# Usb_Hub.net
KiCad netlist of a schematic drawn in EasyEDA Pro
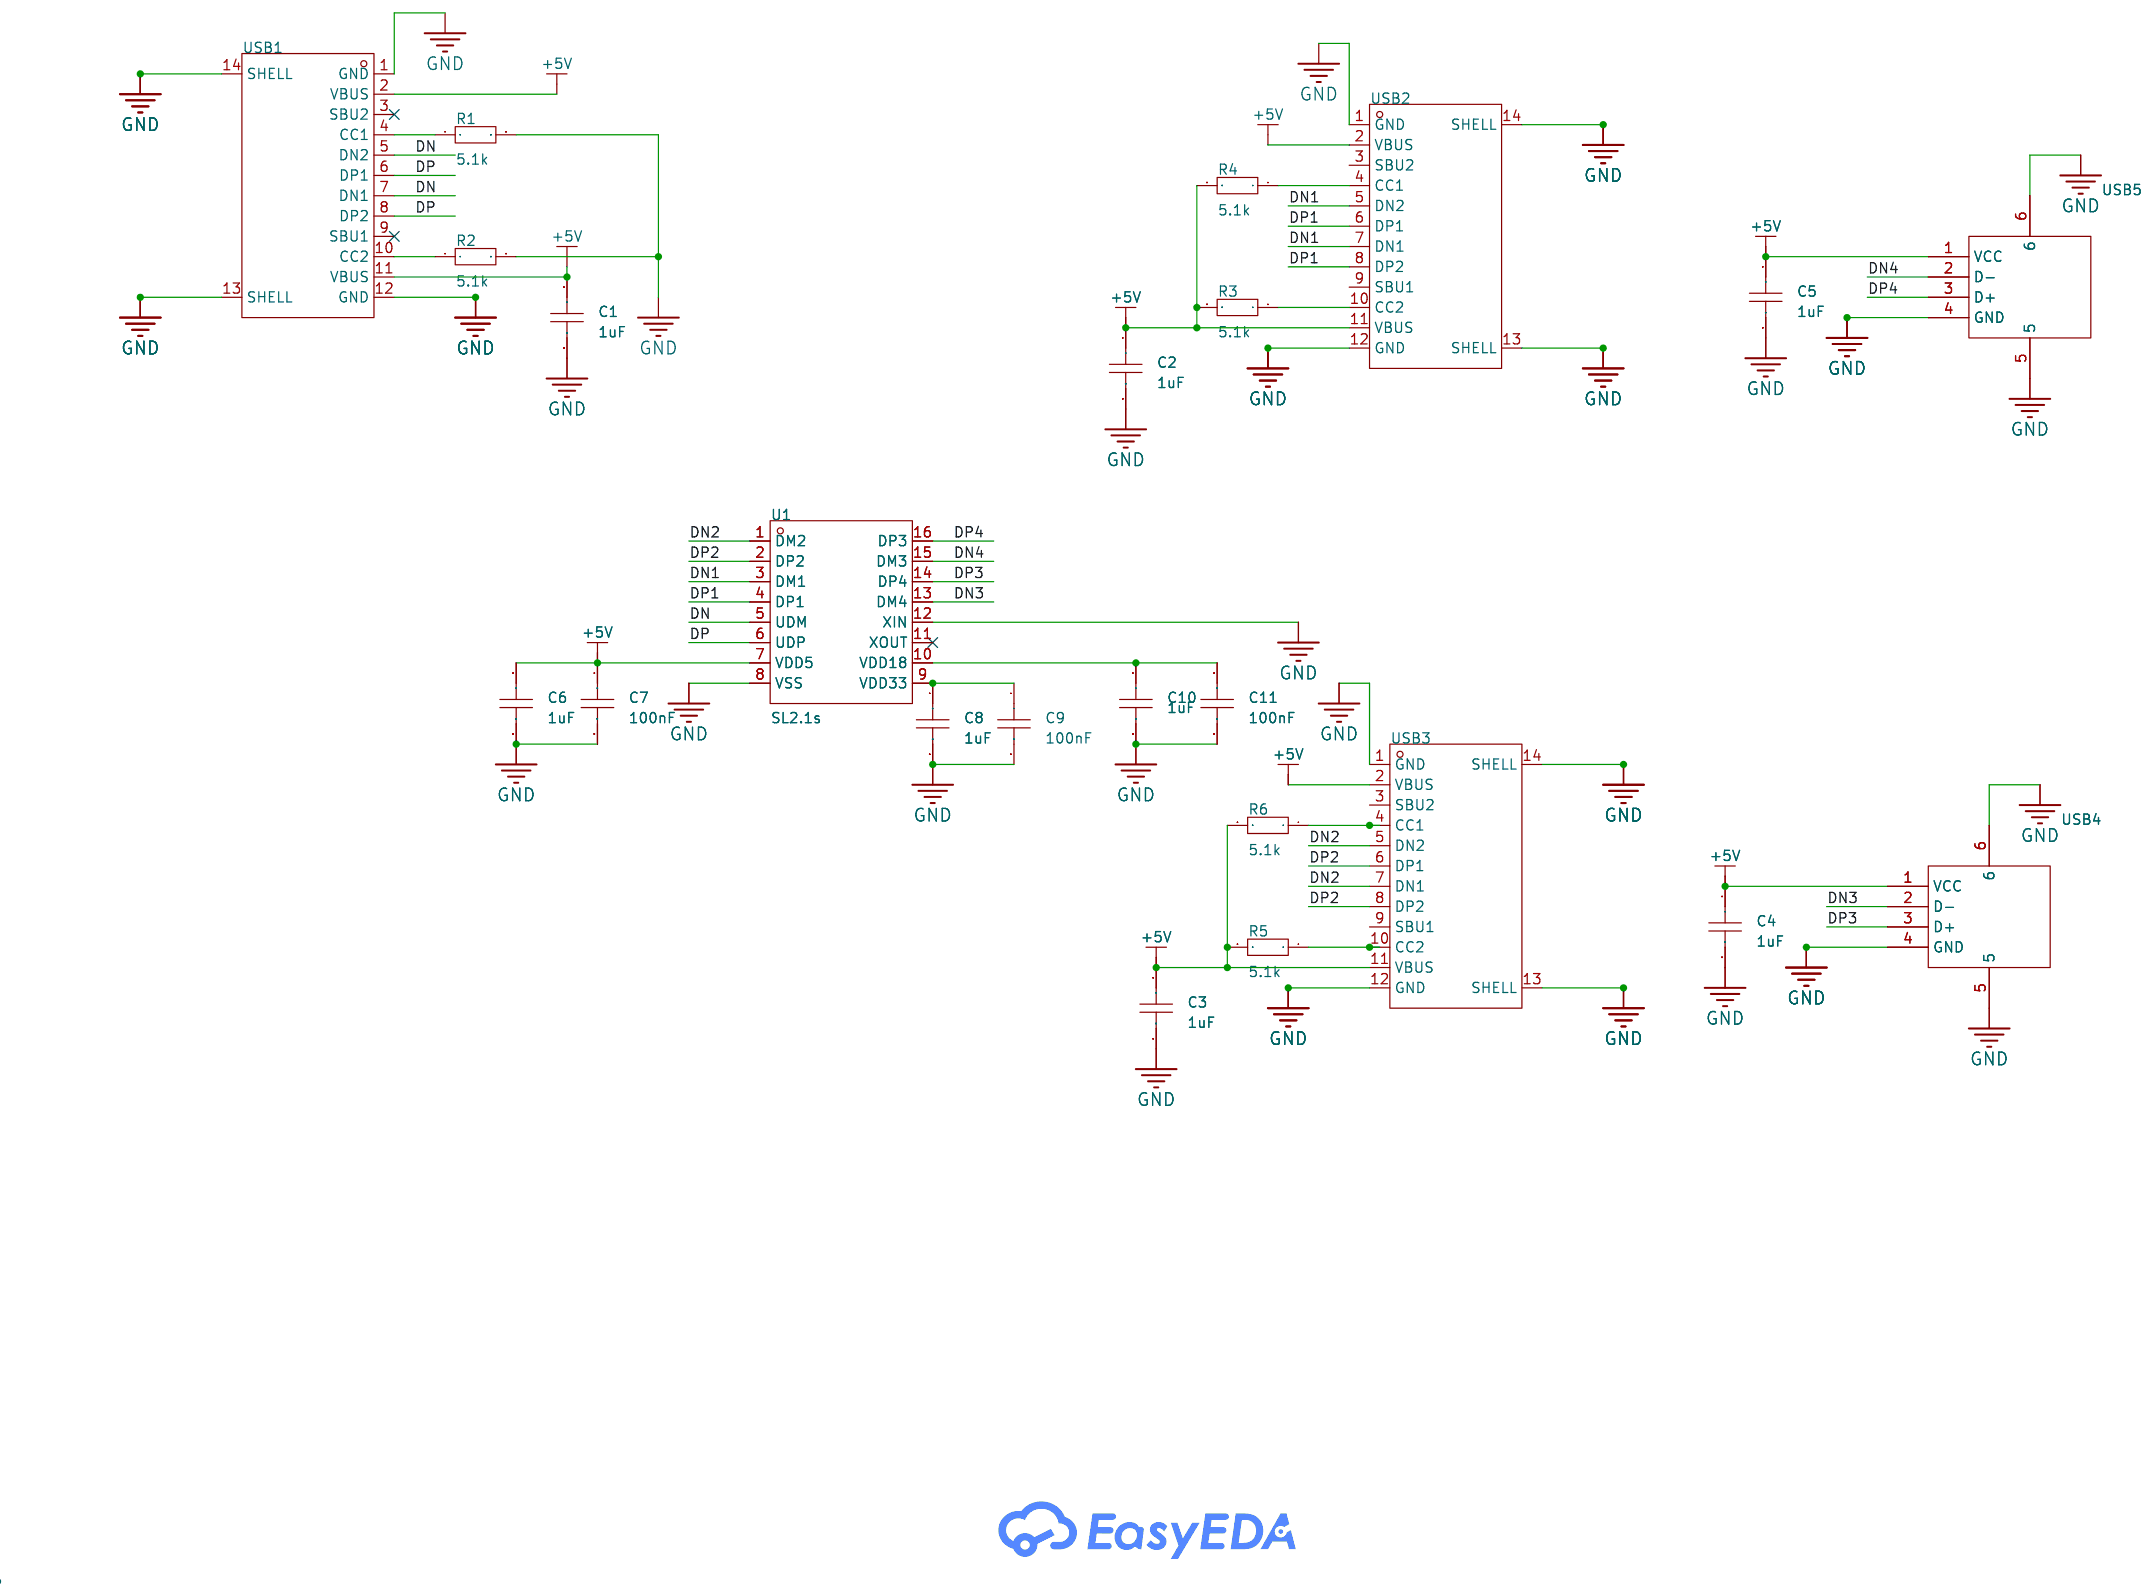
[diagram p0: schematic sheet]

(export (version "E")
  (design (tool "Eeschema 10.0.6"))
  (components
    (comp (ref "C1") (value "1uF") (footprint "easyedapro:C0603") (libsource (lib "easyedapro") (part "CAP")))
    (comp (ref "C2") (value "1uF") (footprint "easyedapro:C0603") (libsource (lib "easyedapro") (part "CAP")))
    (comp (ref "C3") (value "1uF") (footprint "easyedapro:C0603") (libsource (lib "easyedapro") (part "CAP")))
    (comp (ref "C4") (value "1uF") (footprint "easyedapro:C0603") (libsource (lib "easyedapro") (part "CAP")))
    (comp (ref "C5") (value "1uF") (footprint "easyedapro:C0603") (libsource (lib "easyedapro") (part "CAP")))
    (comp (ref "C6") (value "1uF") (footprint "easyedapro:C0603") (libsource (lib "easyedapro") (part "CAP")))
    (comp (ref "C7")
      (value "100nF")
      (footprint "easyedapro:C0603")
      (libsource (lib "easyedapro") (part "CAP"))
    )
    (comp (ref "C8") (value "1uF") (footprint "easyedapro:C0603") (libsource (lib "easyedapro") (part "CAP")))
    (comp (ref "C9")
      (value "100nF")
      (footprint "easyedapro:C0603")
      (libsource (lib "easyedapro") (part "CAP"))
    )
    (comp (ref "C10")
      (value "1uF")
      (footprint "easyedapro:C0603")
      (libsource (lib "easyedapro") (part "CAP"))
    )
    (comp (ref "C11")
      (value "100nF")
      (footprint "easyedapro:C0603")
      (libsource (lib "easyedapro") (part "CAP"))
    )
    (comp (ref "R1")
      (value "5.1k")
      (footprint "easyedapro:R0603")
      (libsource (lib "easyedapro") (part "Res"))
    )
    (comp (ref "R2")
      (value "5.1k")
      (footprint "easyedapro:R0603")
      (libsource (lib "easyedapro") (part "Res"))
    )
    (comp (ref "R3")
      (value "5.1k")
      (footprint "easyedapro:R0603")
      (libsource (lib "easyedapro") (part "Res"))
    )
    (comp (ref "R4")
      (value "5.1k")
      (footprint "easyedapro:R0603")
      (libsource (lib "easyedapro") (part "Res"))
    )
    (comp (ref "R5")
      (value "5.1k")
      (footprint "easyedapro:R0603")
      (libsource (lib "easyedapro") (part "Res"))
    )
    (comp (ref "R6")
      (value "5.1k")
      (footprint "easyedapro:R0603")
      (libsource (lib "easyedapro") (part "Res"))
    )
    (comp (ref "U1")
      (value "SL2.1s")
      (footprint "easyedapro:SSOP-16_L4.6-W2.6-P0.53-LS4.0-BL")
      (fields (field (name "Manufacturer") "CoreChips(和芯润德)"))
      (libsource (lib "easyedapro") (part "SL2.1S"))
    )
    (comp (ref "USB1")
      (value "TYPE-C 16PIN 2MD(073)")
      (footprint "easyedapro:USB-C-SMD_TYPE-C-6PIN-2MD-073")
      (fields (field (name "Manufacturer") "SHOU HAN(首韩)"))
      (libsource (lib "easyedapro") (part "TYPE-C 16PIN 2MD(073)"))
    )
    (comp (ref "USB2")
      (value "TYPE-C 16PIN 2MD(073)")
      (footprint "easyedapro:USB-C-SMD_TYPE-C-6PIN-2MD-073")
      (fields (field (name "Manufacturer") "SHOU HAN(首韩)"))
      (libsource (lib "easyedapro") (part "TYPE-C 16PIN 2MD(073)"))
    )
    (comp (ref "USB3")
      (value "TYPE-C 16PIN 2MD(073)")
      (footprint "easyedapro:USB-C-SMD_TYPE-C-6PIN-2MD-073")
      (fields (field (name "Manufacturer") "SHOU HAN(首韩)"))
      (libsource (lib "easyedapro") (part "TYPE-C 16PIN 2MD(073)"))
    )
    (comp (ref "USB4")
      (value "10.0 QHHTZB6.3")
      (footprint "easyedapro:USB-A-TH_10.0QHHTZB6.3")
      (fields (field (name "Manufacturer") "SHOU HAN(首韩)"))
      (libsource (lib "easyedapro") (part "10.0 QHHTZB6.3"))
    )
    (comp (ref "USB5")
      (value "10.0 QHHTZB6.3")
      (footprint "easyedapro:USB-A-TH_10.0QHHTZB6.3")
      (fields (field (name "Manufacturer") "SHOU HAN(首韩)"))
      (libsource (lib "easyedapro") (part "10.0 QHHTZB6.3"))
    )
  )
  (nets
    (net (code "1") (name "+5V") (class "Default")
      (node (ref "C1") (pin "1") (pinfunction "1_1") (pintype "input"))
      (node (ref "C2") (pin "1") (pinfunction "1_1") (pintype "input"))
      (node (ref "C3") (pin "1") (pinfunction "1_1") (pintype "input"))
      (node (ref "C4") (pin "1") (pinfunction "1_1") (pintype "input"))
      (node (ref "C5") (pin "1") (pinfunction "1_1") (pintype "input"))
      (node (ref "C6") (pin "1") (pinfunction "1_1") (pintype "input"))
      (node (ref "C7") (pin "1") (pinfunction "1_1") (pintype "input"))
      (node (ref "R3") (pin "2") (pinfunction "2_2") (pintype "input"))
      (node (ref "R4") (pin "2") (pinfunction "2_2") (pintype "input"))
      (node (ref "R5") (pin "2") (pinfunction "2_2") (pintype "input"))
      (node (ref "R6") (pin "2") (pinfunction "2_2") (pintype "input"))
      (node (ref "U1") (pin "7") (pinfunction "VDD5_7") (pintype "unspecified"))
      (node (ref "USB1") (pin "11") (pinfunction "VBUS_11") (pintype "unspecified"))
      (node (ref "USB1") (pin "2") (pinfunction "VBUS_2") (pintype "unspecified"))
      (node (ref "USB2") (pin "11") (pinfunction "VBUS_11") (pintype "unspecified"))
      (node (ref "USB2") (pin "2") (pinfunction "VBUS_2") (pintype "unspecified"))
      (node (ref "USB3") (pin "11") (pinfunction "VBUS_11") (pintype "unspecified"))
      (node (ref "USB3") (pin "2") (pinfunction "VBUS_2") (pintype "unspecified"))
      (node (ref "USB4") (pin "1") (pinfunction "VCC_1") (pintype "unspecified"))
      (node (ref "USB5") (pin "1") (pinfunction "VCC_1") (pintype "unspecified"))
    )
    (net (code "2") (name "/DN") (class "Default")
      (node (ref "U1") (pin "5") (pinfunction "UDM_5") (pintype "unspecified"))
      (node (ref "USB1") (pin "5") (pinfunction "DN2_5") (pintype "unspecified"))
      (node (ref "USB1") (pin "7") (pinfunction "DN1_7") (pintype "unspecified"))
    )
    (net (code "3") (name "/DN1") (class "Default")
      (node (ref "U1") (pin "3") (pinfunction "DM1_3") (pintype "unspecified"))
      (node (ref "USB2") (pin "5") (pinfunction "DN2_5") (pintype "unspecified"))
      (node (ref "USB2") (pin "7") (pinfunction "DN1_7") (pintype "unspecified"))
    )
    (net (code "4") (name "/DN2") (class "Default")
      (node (ref "U1") (pin "1") (pinfunction "DM2_1") (pintype "unspecified"))
      (node (ref "USB3") (pin "5") (pinfunction "DN2_5") (pintype "unspecified"))
      (node (ref "USB3") (pin "7") (pinfunction "DN1_7") (pintype "unspecified"))
    )
    (net (code "5") (name "/DN3") (class "Default")
      (node (ref "U1") (pin "13") (pinfunction "DM4_13") (pintype "unspecified"))
      (node (ref "USB4") (pin "2") (pinfunction "D-_2") (pintype "unspecified"))
    )
    (net (code "6") (name "/DN4") (class "Default")
      (node (ref "U1") (pin "15") (pinfunction "DM3_15") (pintype "unspecified"))
      (node (ref "USB5") (pin "2") (pinfunction "D-_2") (pintype "unspecified"))
    )
    (net (code "7") (name "/DP") (class "Default")
      (node (ref "U1") (pin "6") (pinfunction "UDP_6") (pintype "unspecified"))
      (node (ref "USB1") (pin "6") (pinfunction "DP1_6") (pintype "unspecified"))
      (node (ref "USB1") (pin "8") (pinfunction "DP2_8") (pintype "unspecified"))
    )
    (net (code "8") (name "/DP1") (class "Default")
      (node (ref "U1") (pin "4") (pinfunction "DP1_4") (pintype "unspecified"))
      (node (ref "USB2") (pin "6") (pinfunction "DP1_6") (pintype "unspecified"))
      (node (ref "USB2") (pin "8") (pinfunction "DP2_8") (pintype "unspecified"))
    )
    (net (code "9") (name "/DP2") (class "Default")
      (node (ref "U1") (pin "2") (pinfunction "DP2_2") (pintype "unspecified"))
      (node (ref "USB3") (pin "6") (pinfunction "DP1_6") (pintype "unspecified"))
      (node (ref "USB3") (pin "8") (pinfunction "DP2_8") (pintype "unspecified"))
    )
    (net (code "10") (name "/DP3") (class "Default")
      (node (ref "U1") (pin "14") (pinfunction "DP4_14") (pintype "unspecified"))
      (node (ref "USB4") (pin "3") (pinfunction "D+_3") (pintype "unspecified"))
    )
    (net (code "11") (name "/DP4") (class "Default")
      (node (ref "U1") (pin "16") (pinfunction "DP3_16") (pintype "unspecified"))
      (node (ref "USB5") (pin "3") (pinfunction "D+_3") (pintype "unspecified"))
    )
    (net (code "12") (name "GND") (class "Default")
      (node (ref "C1") (pin "2") (pinfunction "2_2") (pintype "input"))
      (node (ref "C10") (pin "2") (pinfunction "2_2") (pintype "input"))
      (node (ref "C11") (pin "2") (pinfunction "2_2") (pintype "input"))
      (node (ref "C2") (pin "2") (pinfunction "2_2") (pintype "input"))
      (node (ref "C3") (pin "2") (pinfunction "2_2") (pintype "input"))
      (node (ref "C4") (pin "2") (pinfunction "2_2") (pintype "input"))
      (node (ref "C5") (pin "2") (pinfunction "2_2") (pintype "input"))
      (node (ref "C6") (pin "2") (pinfunction "2_2") (pintype "input"))
      (node (ref "C7") (pin "2") (pinfunction "2_2") (pintype "input"))
      (node (ref "C8") (pin "2") (pinfunction "2_2") (pintype "input"))
      (node (ref "C9") (pin "2") (pinfunction "2_2") (pintype "input"))
      (node (ref "R1") (pin "2") (pinfunction "2_2") (pintype "input"))
      (node (ref "R2") (pin "2") (pinfunction "2_2") (pintype "input"))
      (node (ref "U1") (pin "12") (pinfunction "XIN_12") (pintype "unspecified"))
      (node (ref "U1") (pin "8") (pinfunction "VSS_8") (pintype "unspecified"))
      (node (ref "USB1") (pin "1") (pinfunction "GND_1") (pintype "unspecified"))
      (node (ref "USB1") (pin "12") (pinfunction "GND_12") (pintype "unspecified"))
      (node (ref "USB1") (pin "13") (pinfunction "SHELL_13") (pintype "unspecified"))
      (node (ref "USB1") (pin "14") (pinfunction "SHELL_14") (pintype "unspecified"))
      (node (ref "USB2") (pin "1") (pinfunction "GND_1") (pintype "unspecified"))
      (node (ref "USB2") (pin "12") (pinfunction "GND_12") (pintype "unspecified"))
      (node (ref "USB2") (pin "13") (pinfunction "SHELL_13") (pintype "unspecified"))
      (node (ref "USB2") (pin "14") (pinfunction "SHELL_14") (pintype "unspecified"))
      (node (ref "USB3") (pin "1") (pinfunction "GND_1") (pintype "unspecified"))
      (node (ref "USB3") (pin "12") (pinfunction "GND_12") (pintype "unspecified"))
      (node (ref "USB3") (pin "13") (pinfunction "SHELL_13") (pintype "unspecified"))
      (node (ref "USB3") (pin "14") (pinfunction "SHELL_14") (pintype "unspecified"))
      (node (ref "USB4") (pin "4") (pinfunction "GND_4") (pintype "unspecified"))
      (node (ref "USB4") (pin "5") (pinfunction "5_5") (pintype "unspecified"))
      (node (ref "USB4") (pin "6") (pinfunction "6_6") (pintype "unspecified"))
      (node (ref "USB5") (pin "4") (pinfunction "GND_4") (pintype "unspecified"))
      (node (ref "USB5") (pin "5") (pinfunction "5_5") (pintype "unspecified"))
      (node (ref "USB5") (pin "6") (pinfunction "6_6") (pintype "unspecified"))
    )
    (net (code "13") (name "Net-(U1-VDD18)") (class "Default")
      (node (ref "C10") (pin "1") (pinfunction "1_1") (pintype "input"))
      (node (ref "C11") (pin "1") (pinfunction "1_1") (pintype "input"))
      (node (ref "U1") (pin "10") (pinfunction "VDD18_10") (pintype "unspecified"))
    )
    (net (code "14") (name "Net-(U1-VDD33)") (class "Default")
      (node (ref "C8") (pin "1") (pinfunction "1_1") (pintype "input"))
      (node (ref "C9") (pin "1") (pinfunction "1_1") (pintype "input"))
      (node (ref "U1") (pin "9") (pinfunction "VDD33_9") (pintype "unspecified"))
    )
    (net (code "15") (name "Net-(USB1-CC1)") (class "Default")
      (node (ref "R1") (pin "1") (pinfunction "1_1") (pintype "input"))
      (node (ref "USB1") (pin "4") (pinfunction "CC1_4") (pintype "unspecified"))
    )
    (net (code "16") (name "Net-(USB1-CC2)") (class "Default")
      (node (ref "R2") (pin "1") (pinfunction "1_1") (pintype "input"))
      (node (ref "USB1") (pin "10") (pinfunction "CC2_10") (pintype "unspecified"))
    )
    (net (code "17") (name "Net-(USB2-CC1)") (class "Default")
      (node (ref "R4") (pin "1") (pinfunction "1_1") (pintype "input"))
      (node (ref "USB2") (pin "4") (pinfunction "CC1_4") (pintype "unspecified"))
    )
    (net (code "18") (name "Net-(USB2-CC2)") (class "Default")
      (node (ref "R3") (pin "1") (pinfunction "1_1") (pintype "input"))
      (node (ref "USB2") (pin "10") (pinfunction "CC2_10") (pintype "unspecified"))
    )
    (net (code "19") (name "Net-(USB3-CC1)") (class "Default")
      (node (ref "R6") (pin "1") (pinfunction "1_1") (pintype "input"))
      (node (ref "USB3") (pin "4") (pinfunction "CC1_4") (pintype "unspecified"))
    )
    (net (code "20") (name "Net-(USB3-CC2)") (class "Default")
      (node (ref "R5") (pin "1") (pinfunction "1_1") (pintype "input"))
      (node (ref "USB3") (pin "10") (pinfunction "CC2_10") (pintype "unspecified"))
    )
    (net (code "21") (name "unconnected-(U1-XOUT-Pad11)") (class "Default")
      (node (ref "U1") (pin "11") (pinfunction "XOUT_11") (pintype "unspecified+no_connect"))
    )
    (net (code "22") (name "unconnected-(USB1-SBU1-Pad9)") (class "Default")
      (node (ref "USB1") (pin "9") (pinfunction "SBU1_9") (pintype "unspecified+no_connect"))
    )
    (net (code "23") (name "unconnected-(USB1-SBU2-Pad3)") (class "Default")
      (node (ref "USB1") (pin "3") (pinfunction "SBU2_3") (pintype "unspecified+no_connect"))
    )
    (net (code "24") (name "unconnected-(USB2-SBU1-Pad9)") (class "Default")
      (node (ref "USB2") (pin "9") (pinfunction "SBU1_9") (pintype "unspecified"))
    )
    (net (code "25") (name "unconnected-(USB2-SBU2-Pad3)") (class "Default")
      (node (ref "USB2") (pin "3") (pinfunction "SBU2_3") (pintype "unspecified"))
    )
    (net (code "26") (name "unconnected-(USB3-SBU1-Pad9)") (class "Default")
      (node (ref "USB3") (pin "9") (pinfunction "SBU1_9") (pintype "unspecified"))
    )
    (net (code "27") (name "unconnected-(USB3-SBU2-Pad3)") (class "Default")
      (node (ref "USB3") (pin "3") (pinfunction "SBU2_3") (pintype "unspecified"))
    )
  )
)
